# SNES_Jukebox.net
KiCad netlist of a schematic drawn in EAGLE
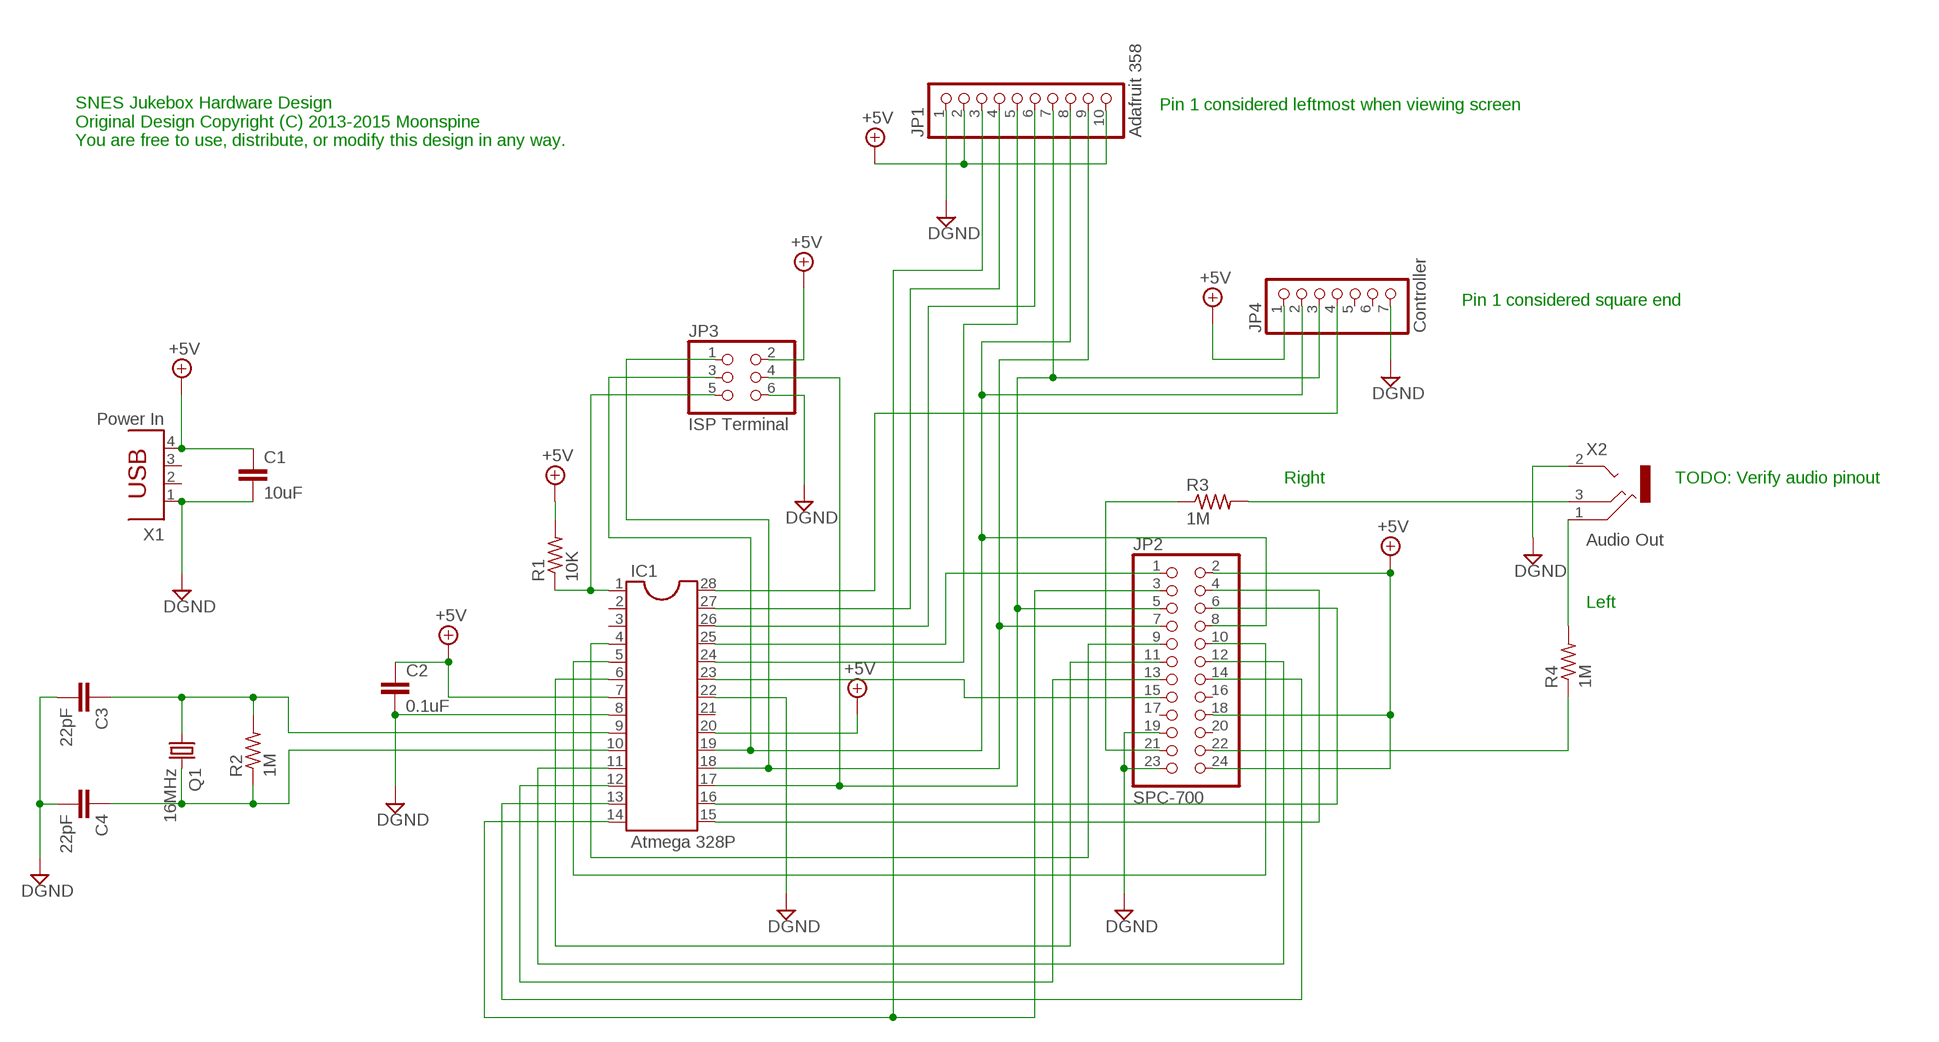
[diagram p0: schematic, sheet 1]

(export (version "E")
  (design (tool "Eeschema 10.0.6"))
  (components
    (comp (ref "C1")
      (value "10uF")
      (footprint "eagle-import:C025-025X050")
      (libsource (lib "eagle-import") (part "C-EU025-025X050"))
    )
    (comp (ref "C2")
      (value "0.1uF")
      (footprint "eagle-import:C025-025X050")
      (libsource (lib "eagle-import") (part "C-EU025-025X050"))
    )
    (comp (ref "C3")
      (value "22pF")
      (footprint "eagle-import:C025-025X050")
      (libsource (lib "eagle-import") (part "C-EU025-025X050"))
    )
    (comp (ref "C4")
      (value "22pF")
      (footprint "eagle-import:C025-025X050")
      (libsource (lib "eagle-import") (part "C-EU025-025X050"))
    )
    (comp (ref "IC1")
      (value "Atmega 328P")
      (footprint "eagle-import:DIL28-3")
      (libsource (lib "eagle-import") (part "DIL28-3"))
    )
    (comp (ref "JP1")
      (value "Adafruit 358")
      (footprint "eagle-import:1X10")
      (libsource (lib "eagle-import") (part "PINHD-1X10"))
    )
    (comp (ref "JP2")
      (value "SPC-700")
      (footprint "eagle-import:2X12")
      (libsource (lib "eagle-import") (part "PINHD-2X12"))
    )
    (comp (ref "JP3")
      (value "ISP Terminal")
      (footprint "eagle-import:2X03")
      (libsource (lib "eagle-import") (part "PINHD-2X3"))
    )
    (comp (ref "JP4")
      (value "Controller")
      (footprint "eagle-import:1X07")
      (libsource (lib "eagle-import") (part "PINHD-1X7"))
    )
    (comp (ref "Q1")
      (value "16MHz")
      (footprint "eagle-import:HC49_S")
      (libsource (lib "eagle-import") (part "CRYSTALHC49S"))
    )
    (comp (ref "R1")
      (value "10K")
      (footprint "eagle-import:0207_10")
      (libsource (lib "eagle-import") (part "R-US_0207/10"))
    )
    (comp (ref "R2")
      (value "1M")
      (footprint "eagle-import:0207_10")
      (libsource (lib "eagle-import") (part "R-US_0207/10"))
    )
    (comp (ref "R3")
      (value "1M")
      (footprint "eagle-import:0207_10")
      (libsource (lib "eagle-import") (part "R-US_0207/10"))
    )
    (comp (ref "R4")
      (value "1M")
      (footprint "eagle-import:0207_10")
      (libsource (lib "eagle-import") (part "R-US_0207/10"))
    )
    (comp (ref "X1")
      (value "Power In")
      (footprint "eagle-import:PN87520")
      (libsource (lib "eagle-import") (part "PN87520"))
    )
    (comp (ref "X2")
      (value "Audio Out")
      (footprint "eagle-import:1503_02")
      (libsource (lib "eagle-import") (part "1503_02"))
    )
  )
  (nets
    (net (code "1") (name "+5V") (class "Default")
      (node (ref "C1") (pin "1") (pinfunction "1_1") (pintype "passive"))
      (node (ref "C2") (pin "1") (pinfunction "1_1") (pintype "passive"))
      (node (ref "IC1") (pin "20") (pinfunction "20_20") (pintype "passive"))
      (node (ref "IC1") (pin "7") (pinfunction "7_7") (pintype "passive"))
      (node (ref "JP1") (pin "10") (pinfunction "10_10") (pintype "passive"))
      (node (ref "JP1") (pin "2") (pinfunction "2_2") (pintype "passive"))
      (node (ref "JP2") (pin "18") (pinfunction "18_18") (pintype "passive"))
      (node (ref "JP2") (pin "2") (pinfunction "2_2") (pintype "passive"))
      (node (ref "JP2") (pin "24") (pinfunction "24_24") (pintype "passive"))
      (node (ref "JP3") (pin "2") (pinfunction "2_2") (pintype "passive"))
      (node (ref "JP4") (pin "1") (pinfunction "1_1") (pintype "passive"))
      (node (ref "R1") (pin "2") (pinfunction "2_2") (pintype "passive"))
      (node (ref "X1") (pin "4") (pinfunction "4_4") (pintype "passive"))
    )
    (net (code "2") (name "DGND") (class "Default")
      (node (ref "C1") (pin "2") (pinfunction "2_2") (pintype "passive"))
      (node (ref "C2") (pin "2") (pinfunction "2_2") (pintype "passive"))
      (node (ref "C3") (pin "2") (pinfunction "2_2") (pintype "passive"))
      (node (ref "C4") (pin "2") (pinfunction "2_2") (pintype "passive"))
      (node (ref "IC1") (pin "22") (pinfunction "22_22") (pintype "passive"))
      (node (ref "IC1") (pin "8") (pinfunction "8_8") (pintype "passive"))
      (node (ref "JP1") (pin "1") (pinfunction "1_1") (pintype "passive"))
      (node (ref "JP2") (pin "19") (pinfunction "19_19") (pintype "passive"))
      (node (ref "JP2") (pin "23") (pinfunction "23_23") (pintype "passive"))
      (node (ref "JP3") (pin "6") (pinfunction "6_6") (pintype "passive"))
      (node (ref "JP4") (pin "7") (pinfunction "7_7") (pintype "passive"))
      (node (ref "X1") (pin "1") (pinfunction "1_1") (pintype "passive"))
      (node (ref "X2") (pin "2") (pinfunction "2_2") (pintype "passive"))
    )
    (net (code "3") (name "Net-(C3-Pad1)") (class "Default")
      (node (ref "C3") (pin "1") (pinfunction "1_1") (pintype "passive"))
      (node (ref "IC1") (pin "9") (pinfunction "9_9") (pintype "passive"))
      (node (ref "Q1") (pin "1") (pinfunction "1_1") (pintype "passive"))
      (node (ref "R2") (pin "2") (pinfunction "2_2") (pintype "passive"))
    )
    (net (code "4") (name "Net-(C4-Pad1)") (class "Default")
      (node (ref "C4") (pin "1") (pinfunction "1_1") (pintype "passive"))
      (node (ref "IC1") (pin "10") (pinfunction "10_10") (pintype "passive"))
      (node (ref "Q1") (pin "2") (pinfunction "2_2") (pintype "passive"))
      (node (ref "R2") (pin "1") (pinfunction "1_1") (pintype "passive"))
    )
    (net (code "5") (name "Net-(IC1-Pad1)") (class "Default")
      (node (ref "IC1") (pin "1") (pinfunction "1_1") (pintype "passive"))
      (node (ref "JP3") (pin "5") (pinfunction "5_5") (pintype "passive"))
      (node (ref "R1") (pin "1") (pinfunction "1_1") (pintype "passive"))
    )
    (net (code "6") (name "Net-(IC1-Pad4)") (class "Default")
      (node (ref "IC1") (pin "4") (pinfunction "4_4") (pintype "passive"))
      (node (ref "JP2") (pin "9") (pinfunction "9_9") (pintype "passive"))
    )
    (net (code "7") (name "Net-(IC1-Pad5)") (class "Default")
      (node (ref "IC1") (pin "5") (pinfunction "5_5") (pintype "passive"))
      (node (ref "JP2") (pin "10") (pinfunction "10_10") (pintype "passive"))
    )
    (net (code "8") (name "Net-(IC1-Pad6)") (class "Default")
      (node (ref "IC1") (pin "6") (pinfunction "6_6") (pintype "passive"))
      (node (ref "JP2") (pin "11") (pinfunction "11_11") (pintype "passive"))
    )
    (net (code "9") (name "Net-(IC1-Pad11)") (class "Default")
      (node (ref "IC1") (pin "11") (pinfunction "11_11") (pintype "passive"))
      (node (ref "JP2") (pin "12") (pinfunction "12_12") (pintype "passive"))
    )
    (net (code "10") (name "Net-(IC1-Pad12)") (class "Default")
      (node (ref "IC1") (pin "12") (pinfunction "12_12") (pintype "passive"))
      (node (ref "JP2") (pin "13") (pinfunction "13_13") (pintype "passive"))
    )
    (net (code "11") (name "Net-(IC1-Pad13)") (class "Default")
      (node (ref "IC1") (pin "13") (pinfunction "13_13") (pintype "passive"))
      (node (ref "JP2") (pin "14") (pinfunction "14_14") (pintype "passive"))
    )
    (net (code "12") (name "Net-(IC1-Pad14)") (class "Default")
      (node (ref "IC1") (pin "14") (pinfunction "14_14") (pintype "passive"))
      (node (ref "JP1") (pin "3") (pinfunction "3_3") (pintype "passive"))
      (node (ref "JP2") (pin "3") (pinfunction "3_3") (pintype "passive"))
    )
    (net (code "13") (name "Net-(IC1-Pad15)") (class "Default")
      (node (ref "IC1") (pin "15") (pinfunction "15_15") (pintype "passive"))
      (node (ref "JP2") (pin "4") (pinfunction "4_4") (pintype "passive"))
    )
    (net (code "14") (name "Net-(IC1-Pad16)") (class "Default")
      (node (ref "IC1") (pin "16") (pinfunction "16_16") (pintype "passive"))
      (node (ref "JP2") (pin "6") (pinfunction "6_6") (pintype "passive"))
    )
    (net (code "15") (name "Net-(IC1-Pad17)") (class "Default")
      (node (ref "IC1") (pin "17") (pinfunction "17_17") (pintype "passive"))
      (node (ref "JP1") (pin "7") (pinfunction "7_7") (pintype "passive"))
      (node (ref "JP2") (pin "5") (pinfunction "5_5") (pintype "passive"))
      (node (ref "JP3") (pin "4") (pinfunction "4_4") (pintype "passive"))
      (node (ref "JP4") (pin "3") (pinfunction "3_3") (pintype "passive"))
    )
    (net (code "16") (name "Net-(IC1-Pad18)") (class "Default")
      (node (ref "IC1") (pin "18") (pinfunction "18_18") (pintype "passive"))
      (node (ref "JP1") (pin "9") (pinfunction "9_9") (pintype "passive"))
      (node (ref "JP2") (pin "7") (pinfunction "7_7") (pintype "passive"))
      (node (ref "JP3") (pin "1") (pinfunction "1_1") (pintype "passive"))
    )
    (net (code "17") (name "Net-(IC1-Pad19)") (class "Default")
      (node (ref "IC1") (pin "19") (pinfunction "19_19") (pintype "passive"))
      (node (ref "JP1") (pin "8") (pinfunction "8_8") (pintype "passive"))
      (node (ref "JP2") (pin "8") (pinfunction "8_8") (pintype "passive"))
      (node (ref "JP3") (pin "3") (pinfunction "3_3") (pintype "passive"))
      (node (ref "JP4") (pin "2") (pinfunction "2_2") (pintype "passive"))
    )
    (net (code "18") (name "Net-(IC1-Pad23)") (class "Default")
      (node (ref "IC1") (pin "23") (pinfunction "23_23") (pintype "passive"))
      (node (ref "JP2") (pin "15") (pinfunction "15_15") (pintype "passive"))
    )
    (net (code "19") (name "Net-(IC1-Pad24)") (class "Default")
      (node (ref "IC1") (pin "24") (pinfunction "24_24") (pintype "passive"))
      (node (ref "JP1") (pin "5") (pinfunction "5_5") (pintype "passive"))
    )
    (net (code "20") (name "Net-(IC1-Pad25)") (class "Default")
      (node (ref "IC1") (pin "25") (pinfunction "25_25") (pintype "passive"))
      (node (ref "JP2") (pin "1") (pinfunction "1_1") (pintype "passive"))
    )
    (net (code "21") (name "Net-(IC1-Pad26)") (class "Default")
      (node (ref "IC1") (pin "26") (pinfunction "26_26") (pintype "passive"))
      (node (ref "JP1") (pin "6") (pinfunction "6_6") (pintype "passive"))
    )
    (net (code "22") (name "Net-(IC1-Pad27)") (class "Default")
      (node (ref "IC1") (pin "27") (pinfunction "27_27") (pintype "passive"))
      (node (ref "JP1") (pin "4") (pinfunction "4_4") (pintype "passive"))
    )
    (net (code "23") (name "Net-(IC1-Pad28)") (class "Default")
      (node (ref "IC1") (pin "28") (pinfunction "28_28") (pintype "passive"))
      (node (ref "JP4") (pin "4") (pinfunction "4_4") (pintype "passive"))
    )
    (net (code "24") (name "Net-(JP2-Pad21)") (class "Default")
      (node (ref "JP2") (pin "21") (pinfunction "21_21") (pintype "passive"))
      (node (ref "R3") (pin "1") (pinfunction "1_1") (pintype "passive"))
    )
    (net (code "25") (name "Net-(JP2-Pad22)") (class "Default")
      (node (ref "JP2") (pin "22") (pinfunction "22_22") (pintype "passive"))
      (node (ref "R4") (pin "1") (pinfunction "1_1") (pintype "passive"))
    )
    (net (code "26") (name "Net-(R3-Pad2)") (class "Default")
      (node (ref "R3") (pin "2") (pinfunction "2_2") (pintype "passive"))
      (node (ref "X2") (pin "3") (pinfunction "3_3") (pintype "passive"))
    )
    (net (code "27") (name "Net-(R4-Pad2)") (class "Default")
      (node (ref "R4") (pin "2") (pinfunction "2_2") (pintype "passive"))
      (node (ref "X2") (pin "1") (pinfunction "1_1") (pintype "passive"))
    )
    (net (code "28") (name "unconnected-(IC1-Pad2)") (class "Default")
      (node (ref "IC1") (pin "2") (pinfunction "2_2") (pintype "passive"))
    )
    (net (code "29") (name "unconnected-(IC1-Pad3)") (class "Default")
      (node (ref "IC1") (pin "3") (pinfunction "3_3") (pintype "passive"))
    )
    (net (code "30") (name "unconnected-(IC1-Pad21)") (class "Default")
      (node (ref "IC1") (pin "21") (pinfunction "21_21") (pintype "passive"))
    )
    (net (code "31") (name "unconnected-(JP2-Pad16)") (class "Default")
      (node (ref "JP2") (pin "16") (pinfunction "16_16") (pintype "passive"))
    )
    (net (code "32") (name "unconnected-(JP2-Pad17)") (class "Default")
      (node (ref "JP2") (pin "17") (pinfunction "17_17") (pintype "passive"))
    )
    (net (code "33") (name "unconnected-(JP2-Pad20)") (class "Default")
      (node (ref "JP2") (pin "20") (pinfunction "20_20") (pintype "passive"))
    )
    (net (code "34") (name "unconnected-(JP4-Pad5)") (class "Default")
      (node (ref "JP4") (pin "5") (pinfunction "5_5") (pintype "passive"))
    )
    (net (code "35") (name "unconnected-(JP4-Pad6)") (class "Default")
      (node (ref "JP4") (pin "6") (pinfunction "6_6") (pintype "passive"))
    )
    (net (code "36") (name "unconnected-(X1-Pad2)") (class "Default")
      (node (ref "X1") (pin "2") (pinfunction "2_2") (pintype "passive"))
    )
    (net (code "37") (name "unconnected-(X1-Pad3)") (class "Default")
      (node (ref "X1") (pin "3") (pinfunction "3_3") (pintype "passive"))
    )
    (net (code "38") (name "unconnected-(X2-2-Pad2@2)") (class "Default")
      (node (ref "X2") (pin "2@2") (pinfunction "2_2@2") (pintype "passive"))
    )
  )
)
